# IN-17_tubes.net
KiCad netlist of a schematic drawn in EAGLE
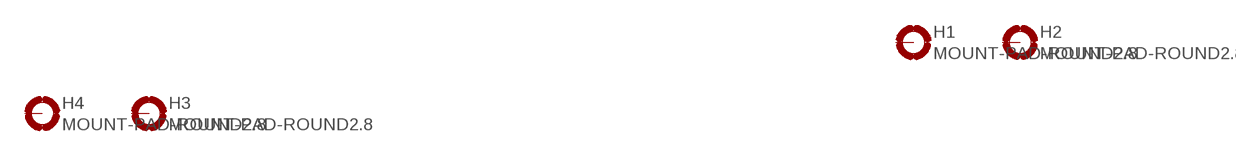
[diagram p0: schematic, sheet 1, part 1 of 2]
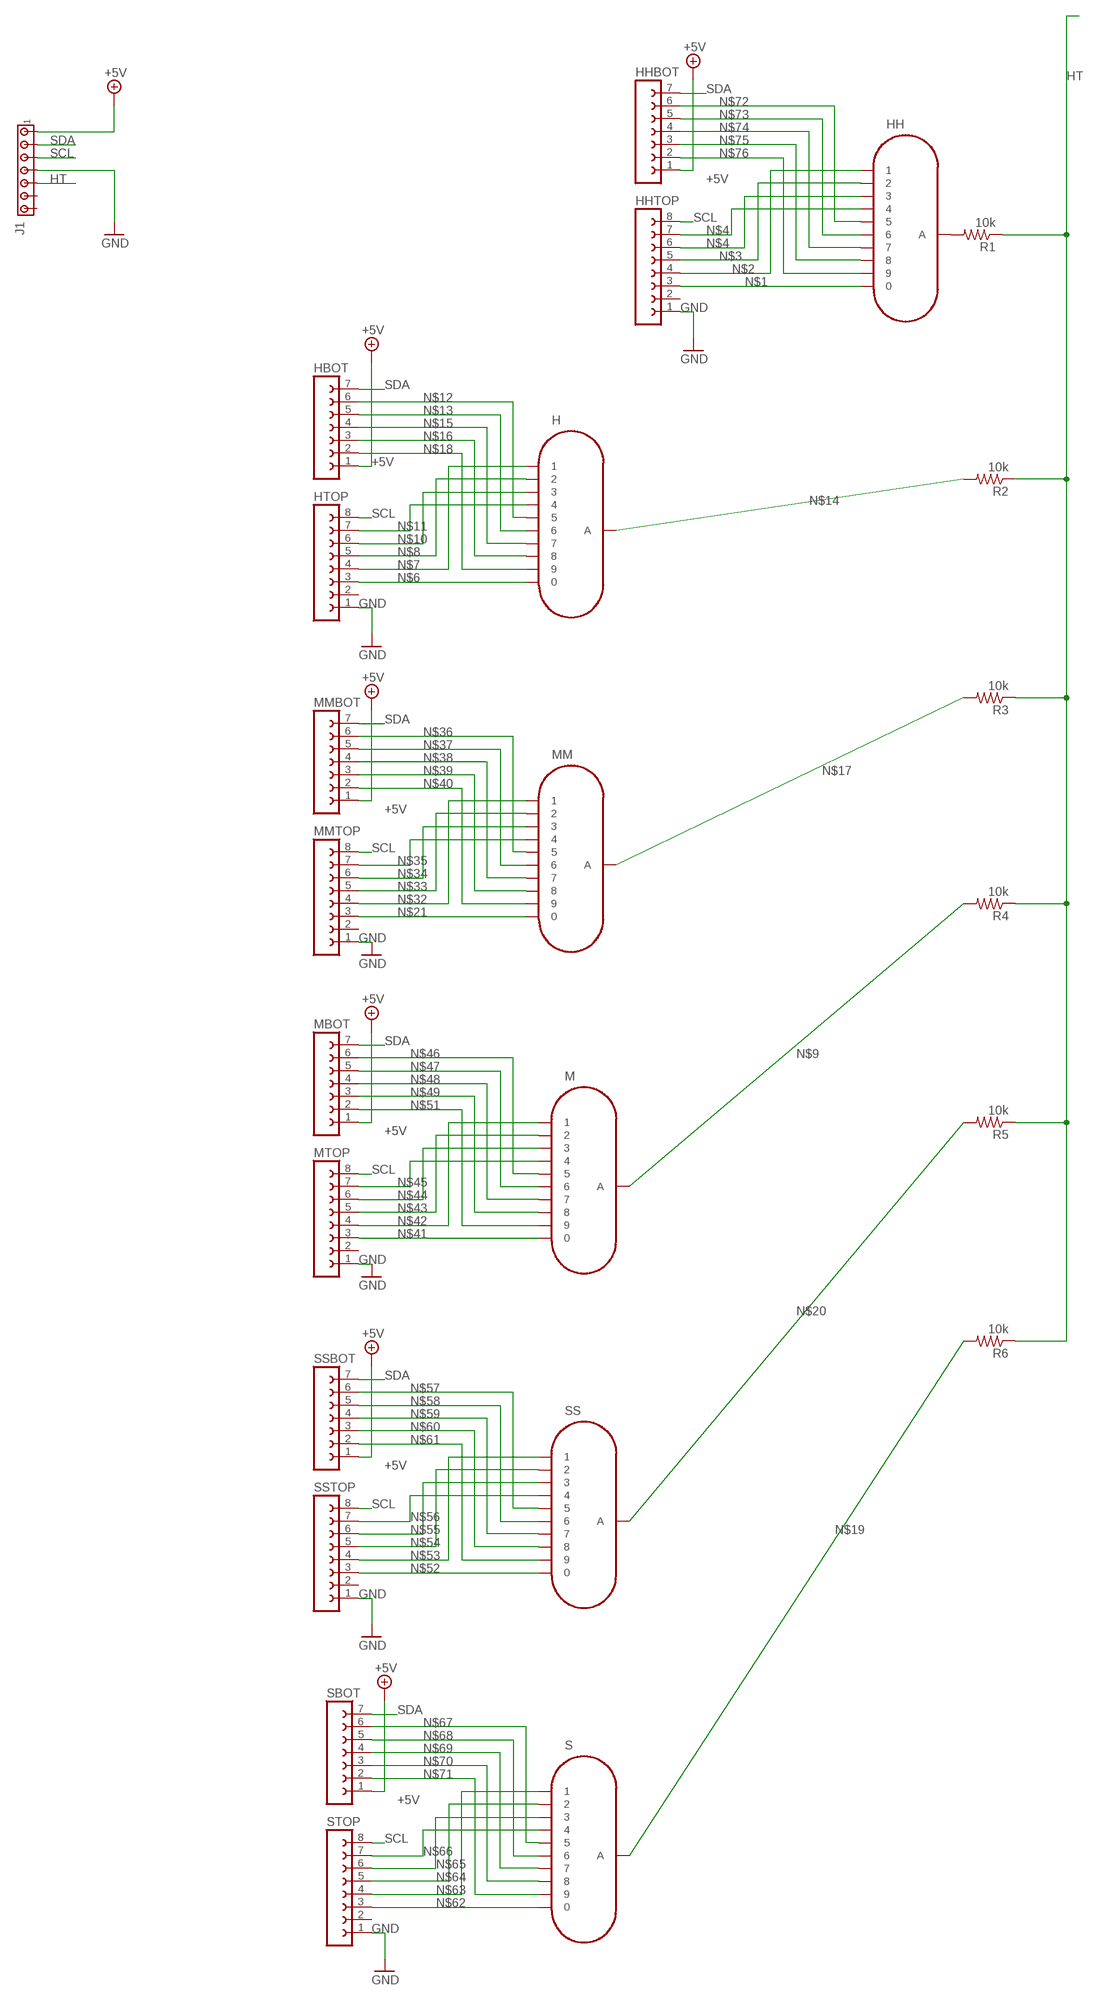
[diagram p1: schematic, sheet 1, part 2 of 2]

(export (version "E")
  (design (tool "Eeschema 10.0.6"))
  (components
    (comp (ref "H")
      (value "IN-17")
      (footprint "eagle-import:IN-17")
      (libsource (lib "eagle-import") (part "IN-17"))
    )
    (comp (ref "H1")
      (value "MOUNT-PAD-ROUND2.8")
      (footprint "eagle-import:2,8-PAD")
      (libsource (lib "eagle-import") (part "MOUNT-PAD-ROUND2.8"))
    )
    (comp (ref "H2")
      (value "MOUNT-PAD-ROUND2.8")
      (footprint "eagle-import:2,8-PAD")
      (libsource (lib "eagle-import") (part "MOUNT-PAD-ROUND2.8"))
    )
    (comp (ref "H3")
      (value "MOUNT-PAD-ROUND2.8")
      (footprint "eagle-import:2,8-PAD")
      (libsource (lib "eagle-import") (part "MOUNT-PAD-ROUND2.8"))
    )
    (comp (ref "H4")
      (value "MOUNT-PAD-ROUND2.8")
      (footprint "eagle-import:2,8-PAD")
      (libsource (lib "eagle-import") (part "MOUNT-PAD-ROUND2.8"))
    )
    (comp (ref "HBOT")
      (value "FE07-1")
      (footprint "eagle-import:FE07")
      (libsource (lib "eagle-import") (part "FE07-1"))
    )
    (comp (ref "HH")
      (value "IN-17")
      (footprint "eagle-import:IN-17")
      (libsource (lib "eagle-import") (part "IN-17"))
    )
    (comp (ref "HHBOT")
      (value "FE07-1")
      (footprint "eagle-import:FE07")
      (libsource (lib "eagle-import") (part "FE07-1"))
    )
    (comp (ref "HHTOP")
      (value "FE08-1")
      (footprint "eagle-import:FE08")
      (libsource (lib "eagle-import") (part "FE08-1"))
    )
    (comp (ref "HTOP")
      (value "FE08-1")
      (footprint "eagle-import:FE08")
      (libsource (lib "eagle-import") (part "FE08-1"))
    )
    (comp (ref "J1")
      (value "MTA07-100")
      (footprint "eagle-import:10X07MTA")
      (libsource (lib "eagle-import") (part "MTA07-100"))
    )
    (comp (ref "M")
      (value "IN-17")
      (footprint "eagle-import:IN-17")
      (libsource (lib "eagle-import") (part "IN-17"))
    )
    (comp (ref "MBOT")
      (value "FE07-1")
      (footprint "eagle-import:FE07")
      (libsource (lib "eagle-import") (part "FE07-1"))
    )
    (comp (ref "MM")
      (value "IN-17")
      (footprint "eagle-import:IN-17")
      (libsource (lib "eagle-import") (part "IN-17"))
    )
    (comp (ref "MMBOT")
      (value "FE07-1")
      (footprint "eagle-import:FE07")
      (libsource (lib "eagle-import") (part "FE07-1"))
    )
    (comp (ref "MMTOP")
      (value "FE08-1")
      (footprint "eagle-import:FE08")
      (libsource (lib "eagle-import") (part "FE08-1"))
    )
    (comp (ref "MTOP")
      (value "FE08-1")
      (footprint "eagle-import:FE08")
      (libsource (lib "eagle-import") (part "FE08-1"))
    )
    (comp (ref "R1")
      (value "10k")
      (footprint "eagle-import:M0805")
      (libsource (lib "eagle-import") (part "R-US_M0805"))
    )
    (comp (ref "R2")
      (value "10k")
      (footprint "eagle-import:M0805")
      (libsource (lib "eagle-import") (part "R-US_M0805"))
    )
    (comp (ref "R3")
      (value "10k")
      (footprint "eagle-import:M0805")
      (libsource (lib "eagle-import") (part "R-US_M0805"))
    )
    (comp (ref "R4")
      (value "10k")
      (footprint "eagle-import:M0805")
      (libsource (lib "eagle-import") (part "R-US_M0805"))
    )
    (comp (ref "R5")
      (value "10k")
      (footprint "eagle-import:M0805")
      (libsource (lib "eagle-import") (part "R-US_M0805"))
    )
    (comp (ref "R6")
      (value "10k")
      (footprint "eagle-import:M0805")
      (libsource (lib "eagle-import") (part "R-US_M0805"))
    )
    (comp (ref "S")
      (value "IN-17")
      (footprint "eagle-import:IN-17")
      (libsource (lib "eagle-import") (part "IN-17"))
    )
    (comp (ref "SBOT")
      (value "FE07-1")
      (footprint "eagle-import:FE07")
      (libsource (lib "eagle-import") (part "FE07-1"))
    )
    (comp (ref "SS")
      (value "IN-17")
      (footprint "eagle-import:IN-17")
      (libsource (lib "eagle-import") (part "IN-17"))
    )
    (comp (ref "SSBOT")
      (value "FE07-1")
      (footprint "eagle-import:FE07")
      (libsource (lib "eagle-import") (part "FE07-1"))
    )
    (comp (ref "SSTOP")
      (value "FE08-1")
      (footprint "eagle-import:FE08")
      (libsource (lib "eagle-import") (part "FE08-1"))
    )
    (comp (ref "STOP")
      (value "FE08-1")
      (footprint "eagle-import:FE08")
      (libsource (lib "eagle-import") (part "FE08-1"))
    )
  )
  (nets
    (net (code "1") (name "+5V") (class "Default")
      (node (ref "HBOT") (pin "1") (pinfunction "1_1") (pintype "passive"))
      (node (ref "HHBOT") (pin "1") (pinfunction "1_1") (pintype "passive"))
      (node (ref "J1") (pin "1") (pinfunction "1_1") (pintype "passive"))
      (node (ref "MBOT") (pin "1") (pinfunction "1_1") (pintype "passive"))
      (node (ref "MMBOT") (pin "1") (pinfunction "1_1") (pintype "passive"))
      (node (ref "SBOT") (pin "1") (pinfunction "1_1") (pintype "passive"))
      (node (ref "SSBOT") (pin "1") (pinfunction "1_1") (pintype "passive"))
    )
    (net (code "2") (name "/HT") (class "Default")
      (node (ref "J1") (pin "5") (pinfunction "5_5") (pintype "passive"))
      (node (ref "R1") (pin "1") (pinfunction "1_1") (pintype "passive"))
      (node (ref "R2") (pin "1") (pinfunction "1_1") (pintype "passive"))
      (node (ref "R3") (pin "1") (pinfunction "1_1") (pintype "passive"))
      (node (ref "R4") (pin "1") (pinfunction "1_1") (pintype "passive"))
      (node (ref "R5") (pin "1") (pinfunction "1_1") (pintype "passive"))
      (node (ref "R6") (pin "1") (pinfunction "1_1") (pintype "passive"))
    )
    (net (code "3") (name "/N$1") (class "Default")
      (node (ref "HH") (pin "0") (pinfunction "0_0") (pintype "bidirectional"))
      (node (ref "HHTOP") (pin "3") (pinfunction "3_3") (pintype "passive"))
    )
    (net (code "4") (name "/N$2") (class "Default")
      (node (ref "HH") (pin "1") (pinfunction "1_1") (pintype "bidirectional"))
      (node (ref "HHTOP") (pin "4") (pinfunction "4_4") (pintype "passive"))
    )
    (net (code "5") (name "/N$3") (class "Default")
      (node (ref "HH") (pin "2") (pinfunction "2_2") (pintype "bidirectional"))
      (node (ref "HHTOP") (pin "5") (pinfunction "5_5") (pintype "passive"))
    )
    (net (code "6") (name "/N$4") (class "Default")
      (node (ref "HH") (pin "3") (pinfunction "3_3") (pintype "bidirectional"))
      (node (ref "HHTOP") (pin "6") (pinfunction "6_6") (pintype "passive"))
    )
    (net (code "7") (name "/N$6") (class "Default")
      (node (ref "H") (pin "0") (pinfunction "0_0") (pintype "bidirectional"))
      (node (ref "HTOP") (pin "3") (pinfunction "3_3") (pintype "passive"))
    )
    (net (code "8") (name "/N$7") (class "Default")
      (node (ref "H") (pin "1") (pinfunction "1_1") (pintype "bidirectional"))
      (node (ref "HTOP") (pin "4") (pinfunction "4_4") (pintype "passive"))
    )
    (net (code "9") (name "/N$8") (class "Default")
      (node (ref "H") (pin "2") (pinfunction "2_2") (pintype "bidirectional"))
      (node (ref "HTOP") (pin "5") (pinfunction "5_5") (pintype "passive"))
    )
    (net (code "10") (name "/N$9") (class "Default")
      (node (ref "M") (pin "A") (pinfunction "A_A") (pintype "bidirectional"))
      (node (ref "R4") (pin "2") (pinfunction "2_2") (pintype "passive"))
    )
    (net (code "11") (name "/N$10") (class "Default")
      (node (ref "H") (pin "3") (pinfunction "3_3") (pintype "bidirectional"))
      (node (ref "HTOP") (pin "6") (pinfunction "6_6") (pintype "passive"))
    )
    (net (code "12") (name "/N$11") (class "Default")
      (node (ref "H") (pin "4") (pinfunction "4_4") (pintype "bidirectional"))
      (node (ref "HTOP") (pin "7") (pinfunction "7_7") (pintype "passive"))
    )
    (net (code "13") (name "/N$12") (class "Default")
      (node (ref "H") (pin "5") (pinfunction "5_5") (pintype "bidirectional"))
      (node (ref "HBOT") (pin "6") (pinfunction "6_6") (pintype "passive"))
    )
    (net (code "14") (name "/N$13") (class "Default")
      (node (ref "H") (pin "6") (pinfunction "6_6") (pintype "bidirectional"))
      (node (ref "HBOT") (pin "5") (pinfunction "5_5") (pintype "passive"))
    )
    (net (code "15") (name "/N$14") (class "Default")
      (node (ref "H") (pin "A") (pinfunction "A_A") (pintype "bidirectional"))
      (node (ref "R2") (pin "2") (pinfunction "2_2") (pintype "passive"))
    )
    (net (code "16") (name "/N$15") (class "Default")
      (node (ref "H") (pin "7") (pinfunction "7_7") (pintype "bidirectional"))
      (node (ref "HBOT") (pin "4") (pinfunction "4_4") (pintype "passive"))
    )
    (net (code "17") (name "/N$16") (class "Default")
      (node (ref "H") (pin "8") (pinfunction "8_8") (pintype "bidirectional"))
      (node (ref "HBOT") (pin "3") (pinfunction "3_3") (pintype "passive"))
    )
    (net (code "18") (name "/N$17") (class "Default")
      (node (ref "MM") (pin "A") (pinfunction "A_A") (pintype "bidirectional"))
      (node (ref "R3") (pin "2") (pinfunction "2_2") (pintype "passive"))
    )
    (net (code "19") (name "/N$18") (class "Default")
      (node (ref "H") (pin "9") (pinfunction "9_9") (pintype "bidirectional"))
      (node (ref "HBOT") (pin "2") (pinfunction "2_2") (pintype "passive"))
    )
    (net (code "20") (name "/N$19") (class "Default")
      (node (ref "R6") (pin "2") (pinfunction "2_2") (pintype "passive"))
      (node (ref "S") (pin "A") (pinfunction "A_A") (pintype "bidirectional"))
    )
    (net (code "21") (name "/N$20") (class "Default")
      (node (ref "R5") (pin "2") (pinfunction "2_2") (pintype "passive"))
      (node (ref "SS") (pin "A") (pinfunction "A_A") (pintype "bidirectional"))
    )
    (net (code "22") (name "/N$21") (class "Default")
      (node (ref "MM") (pin "0") (pinfunction "0_0") (pintype "bidirectional"))
      (node (ref "MMTOP") (pin "3") (pinfunction "3_3") (pintype "passive"))
    )
    (net (code "23") (name "/N$32") (class "Default")
      (node (ref "MM") (pin "1") (pinfunction "1_1") (pintype "bidirectional"))
      (node (ref "MMTOP") (pin "4") (pinfunction "4_4") (pintype "passive"))
    )
    (net (code "24") (name "/N$33") (class "Default")
      (node (ref "MM") (pin "2") (pinfunction "2_2") (pintype "bidirectional"))
      (node (ref "MMTOP") (pin "5") (pinfunction "5_5") (pintype "passive"))
    )
    (net (code "25") (name "/N$34") (class "Default")
      (node (ref "MM") (pin "3") (pinfunction "3_3") (pintype "bidirectional"))
      (node (ref "MMTOP") (pin "6") (pinfunction "6_6") (pintype "passive"))
    )
    (net (code "26") (name "/N$35") (class "Default")
      (node (ref "MM") (pin "4") (pinfunction "4_4") (pintype "bidirectional"))
      (node (ref "MMTOP") (pin "7") (pinfunction "7_7") (pintype "passive"))
    )
    (net (code "27") (name "/N$36") (class "Default")
      (node (ref "MM") (pin "5") (pinfunction "5_5") (pintype "bidirectional"))
      (node (ref "MMBOT") (pin "6") (pinfunction "6_6") (pintype "passive"))
    )
    (net (code "28") (name "/N$37") (class "Default")
      (node (ref "MM") (pin "6") (pinfunction "6_6") (pintype "bidirectional"))
      (node (ref "MMBOT") (pin "5") (pinfunction "5_5") (pintype "passive"))
    )
    (net (code "29") (name "/N$38") (class "Default")
      (node (ref "MM") (pin "7") (pinfunction "7_7") (pintype "bidirectional"))
      (node (ref "MMBOT") (pin "4") (pinfunction "4_4") (pintype "passive"))
    )
    (net (code "30") (name "/N$39") (class "Default")
      (node (ref "MM") (pin "8") (pinfunction "8_8") (pintype "bidirectional"))
      (node (ref "MMBOT") (pin "3") (pinfunction "3_3") (pintype "passive"))
    )
    (net (code "31") (name "/N$40") (class "Default")
      (node (ref "MM") (pin "9") (pinfunction "9_9") (pintype "bidirectional"))
      (node (ref "MMBOT") (pin "2") (pinfunction "2_2") (pintype "passive"))
    )
    (net (code "32") (name "/N$41") (class "Default")
      (node (ref "M") (pin "0") (pinfunction "0_0") (pintype "bidirectional"))
      (node (ref "MTOP") (pin "3") (pinfunction "3_3") (pintype "passive"))
    )
    (net (code "33") (name "/N$42") (class "Default")
      (node (ref "M") (pin "1") (pinfunction "1_1") (pintype "bidirectional"))
      (node (ref "MTOP") (pin "4") (pinfunction "4_4") (pintype "passive"))
    )
    (net (code "34") (name "/N$43") (class "Default")
      (node (ref "M") (pin "2") (pinfunction "2_2") (pintype "bidirectional"))
      (node (ref "MTOP") (pin "5") (pinfunction "5_5") (pintype "passive"))
    )
    (net (code "35") (name "/N$44") (class "Default")
      (node (ref "M") (pin "3") (pinfunction "3_3") (pintype "bidirectional"))
      (node (ref "MTOP") (pin "6") (pinfunction "6_6") (pintype "passive"))
    )
    (net (code "36") (name "/N$45") (class "Default")
      (node (ref "M") (pin "4") (pinfunction "4_4") (pintype "bidirectional"))
      (node (ref "MTOP") (pin "7") (pinfunction "7_7") (pintype "passive"))
    )
    (net (code "37") (name "/N$46") (class "Default")
      (node (ref "M") (pin "5") (pinfunction "5_5") (pintype "bidirectional"))
      (node (ref "MBOT") (pin "6") (pinfunction "6_6") (pintype "passive"))
    )
    (net (code "38") (name "/N$47") (class "Default")
      (node (ref "M") (pin "6") (pinfunction "6_6") (pintype "bidirectional"))
      (node (ref "MBOT") (pin "5") (pinfunction "5_5") (pintype "passive"))
    )
    (net (code "39") (name "/N$48") (class "Default")
      (node (ref "M") (pin "7") (pinfunction "7_7") (pintype "bidirectional"))
      (node (ref "MBOT") (pin "4") (pinfunction "4_4") (pintype "passive"))
    )
    (net (code "40") (name "/N$49") (class "Default")
      (node (ref "M") (pin "8") (pinfunction "8_8") (pintype "bidirectional"))
      (node (ref "MBOT") (pin "3") (pinfunction "3_3") (pintype "passive"))
    )
    (net (code "41") (name "/N$51") (class "Default")
      (node (ref "M") (pin "9") (pinfunction "9_9") (pintype "bidirectional"))
      (node (ref "MBOT") (pin "2") (pinfunction "2_2") (pintype "passive"))
    )
    (net (code "42") (name "/N$52") (class "Default")
      (node (ref "SS") (pin "0") (pinfunction "0_0") (pintype "bidirectional"))
      (node (ref "SSTOP") (pin "3") (pinfunction "3_3") (pintype "passive"))
    )
    (net (code "43") (name "/N$53") (class "Default")
      (node (ref "SS") (pin "1") (pinfunction "1_1") (pintype "bidirectional"))
      (node (ref "SSTOP") (pin "4") (pinfunction "4_4") (pintype "passive"))
    )
    (net (code "44") (name "/N$54") (class "Default")
      (node (ref "SS") (pin "2") (pinfunction "2_2") (pintype "bidirectional"))
      (node (ref "SSTOP") (pin "5") (pinfunction "5_5") (pintype "passive"))
    )
    (net (code "45") (name "/N$55") (class "Default")
      (node (ref "SS") (pin "3") (pinfunction "3_3") (pintype "bidirectional"))
      (node (ref "SSTOP") (pin "6") (pinfunction "6_6") (pintype "passive"))
    )
    (net (code "46") (name "/N$56") (class "Default")
      (node (ref "SS") (pin "4") (pinfunction "4_4") (pintype "bidirectional"))
      (node (ref "SSTOP") (pin "7") (pinfunction "7_7") (pintype "passive"))
    )
    (net (code "47") (name "/N$57") (class "Default")
      (node (ref "SS") (pin "5") (pinfunction "5_5") (pintype "bidirectional"))
      (node (ref "SSBOT") (pin "6") (pinfunction "6_6") (pintype "passive"))
    )
    (net (code "48") (name "/N$58") (class "Default")
      (node (ref "SS") (pin "6") (pinfunction "6_6") (pintype "bidirectional"))
      (node (ref "SSBOT") (pin "5") (pinfunction "5_5") (pintype "passive"))
    )
    (net (code "49") (name "/N$59") (class "Default")
      (node (ref "SS") (pin "7") (pinfunction "7_7") (pintype "bidirectional"))
      (node (ref "SSBOT") (pin "4") (pinfunction "4_4") (pintype "passive"))
    )
    (net (code "50") (name "/N$60") (class "Default")
      (node (ref "SS") (pin "8") (pinfunction "8_8") (pintype "bidirectional"))
      (node (ref "SSBOT") (pin "3") (pinfunction "3_3") (pintype "passive"))
    )
    (net (code "51") (name "/N$61") (class "Default")
      (node (ref "SS") (pin "9") (pinfunction "9_9") (pintype "bidirectional"))
      (node (ref "SSBOT") (pin "2") (pinfunction "2_2") (pintype "passive"))
    )
    (net (code "52") (name "/N$62") (class "Default")
      (node (ref "S") (pin "0") (pinfunction "0_0") (pintype "bidirectional"))
      (node (ref "STOP") (pin "3") (pinfunction "3_3") (pintype "passive"))
    )
    (net (code "53") (name "/N$63") (class "Default")
      (node (ref "S") (pin "1") (pinfunction "1_1") (pintype "bidirectional"))
      (node (ref "STOP") (pin "4") (pinfunction "4_4") (pintype "passive"))
    )
    (net (code "54") (name "/N$64") (class "Default")
      (node (ref "S") (pin "2") (pinfunction "2_2") (pintype "bidirectional"))
      (node (ref "STOP") (pin "5") (pinfunction "5_5") (pintype "passive"))
    )
    (net (code "55") (name "/N$65") (class "Default")
      (node (ref "S") (pin "3") (pinfunction "3_3") (pintype "bidirectional"))
      (node (ref "STOP") (pin "6") (pinfunction "6_6") (pintype "passive"))
    )
    (net (code "56") (name "/N$66") (class "Default")
      (node (ref "S") (pin "4") (pinfunction "4_4") (pintype "bidirectional"))
      (node (ref "STOP") (pin "7") (pinfunction "7_7") (pintype "passive"))
    )
    (net (code "57") (name "/N$67") (class "Default")
      (node (ref "S") (pin "5") (pinfunction "5_5") (pintype "bidirectional"))
      (node (ref "SBOT") (pin "6") (pinfunction "6_6") (pintype "passive"))
    )
    (net (code "58") (name "/N$68") (class "Default")
      (node (ref "S") (pin "6") (pinfunction "6_6") (pintype "bidirectional"))
      (node (ref "SBOT") (pin "5") (pinfunction "5_5") (pintype "passive"))
    )
    (net (code "59") (name "/N$69") (class "Default")
      (node (ref "S") (pin "7") (pinfunction "7_7") (pintype "bidirectional"))
      (node (ref "SBOT") (pin "4") (pinfunction "4_4") (pintype "passive"))
    )
    (net (code "60") (name "/N$70") (class "Default")
      (node (ref "S") (pin "8") (pinfunction "8_8") (pintype "bidirectional"))
      (node (ref "SBOT") (pin "3") (pinfunction "3_3") (pintype "passive"))
    )
    (net (code "61") (name "/N$71") (class "Default")
      (node (ref "S") (pin "9") (pinfunction "9_9") (pintype "bidirectional"))
      (node (ref "SBOT") (pin "2") (pinfunction "2_2") (pintype "passive"))
    )
    (net (code "62") (name "/N$72") (class "Default")
      (node (ref "HH") (pin "5") (pinfunction "5_5") (pintype "bidirectional"))
      (node (ref "HHBOT") (pin "6") (pinfunction "6_6") (pintype "passive"))
    )
    (net (code "63") (name "/N$73") (class "Default")
      (node (ref "HH") (pin "6") (pinfunction "6_6") (pintype "bidirectional"))
      (node (ref "HHBOT") (pin "5") (pinfunction "5_5") (pintype "passive"))
    )
    (net (code "64") (name "/N$74") (class "Default")
      (node (ref "HH") (pin "7") (pinfunction "7_7") (pintype "bidirectional"))
      (node (ref "HHBOT") (pin "4") (pinfunction "4_4") (pintype "passive"))
    )
    (net (code "65") (name "/N$75") (class "Default")
      (node (ref "HH") (pin "8") (pinfunction "8_8") (pintype "bidirectional"))
      (node (ref "HHBOT") (pin "3") (pinfunction "3_3") (pintype "passive"))
    )
    (net (code "66") (name "/N$76") (class "Default")
      (node (ref "HH") (pin "9") (pinfunction "9_9") (pintype "bidirectional"))
      (node (ref "HHBOT") (pin "2") (pinfunction "2_2") (pintype "passive"))
    )
    (net (code "67") (name "/SCL") (class "Default")
      (node (ref "HHTOP") (pin "8") (pinfunction "8_8") (pintype "passive"))
      (node (ref "HTOP") (pin "8") (pinfunction "8_8") (pintype "passive"))
      (node (ref "J1") (pin "3") (pinfunction "3_3") (pintype "passive"))
      (node (ref "MMTOP") (pin "8") (pinfunction "8_8") (pintype "passive"))
      (node (ref "MTOP") (pin "8") (pinfunction "8_8") (pintype "passive"))
      (node (ref "SSTOP") (pin "8") (pinfunction "8_8") (pintype "passive"))
      (node (ref "STOP") (pin "8") (pinfunction "8_8") (pintype "passive"))
    )
    (net (code "68") (name "/SDA") (class "Default")
      (node (ref "HBOT") (pin "7") (pinfunction "7_7") (pintype "passive"))
      (node (ref "HHBOT") (pin "7") (pinfunction "7_7") (pintype "passive"))
      (node (ref "J1") (pin "2") (pinfunction "2_2") (pintype "passive"))
      (node (ref "MBOT") (pin "7") (pinfunction "7_7") (pintype "passive"))
      (node (ref "MMBOT") (pin "7") (pinfunction "7_7") (pintype "passive"))
      (node (ref "SBOT") (pin "7") (pinfunction "7_7") (pintype "passive"))
      (node (ref "SSBOT") (pin "7") (pinfunction "7_7") (pintype "passive"))
    )
    (net (code "69") (name "GND") (class "Default")
      (node (ref "HHTOP") (pin "1") (pinfunction "1_1") (pintype "passive"))
      (node (ref "HTOP") (pin "1") (pinfunction "1_1") (pintype "passive"))
      (node (ref "J1") (pin "4") (pinfunction "4_4") (pintype "passive"))
      (node (ref "MMTOP") (pin "1") (pinfunction "1_1") (pintype "passive"))
      (node (ref "MTOP") (pin "1") (pinfunction "1_1") (pintype "passive"))
      (node (ref "SSTOP") (pin "1") (pinfunction "1_1") (pintype "passive"))
      (node (ref "STOP") (pin "1") (pinfunction "1_1") (pintype "passive"))
    )
    (net (code "70") (name "Net-(HH-Pad4)") (class "Default")
      (node (ref "HH") (pin "4") (pinfunction "4_4") (pintype "bidirectional"))
      (node (ref "HHTOP") (pin "7") (pinfunction "7_7") (pintype "passive"))
    )
    (net (code "71") (name "Net-(HH-PadA)") (class "Default")
      (node (ref "HH") (pin "A") (pinfunction "A_A") (pintype "bidirectional"))
      (node (ref "R1") (pin "2") (pinfunction "2_2") (pintype "passive"))
    )
    (net (code "72") (name "unconnected-(H1-MOUNT-PadB2,8)") (class "Default")
      (node (ref "H1") (pin "B2,8") (pinfunction "MOUNT_B2,8") (pintype "passive"))
    )
    (net (code "73") (name "unconnected-(H2-MOUNT-PadB2,8)") (class "Default")
      (node (ref "H2") (pin "B2,8") (pinfunction "MOUNT_B2,8") (pintype "passive"))
    )
    (net (code "74") (name "unconnected-(H3-MOUNT-PadB2,8)") (class "Default")
      (node (ref "H3") (pin "B2,8") (pinfunction "MOUNT_B2,8") (pintype "passive"))
    )
    (net (code "75") (name "unconnected-(H4-MOUNT-PadB2,8)") (class "Default")
      (node (ref "H4") (pin "B2,8") (pinfunction "MOUNT_B2,8") (pintype "passive"))
    )
    (net (code "76") (name "unconnected-(HHTOP-Pad2)") (class "Default")
      (node (ref "HHTOP") (pin "2") (pinfunction "2_2") (pintype "passive"))
    )
    (net (code "77") (name "unconnected-(HTOP-Pad2)") (class "Default")
      (node (ref "HTOP") (pin "2") (pinfunction "2_2") (pintype "passive"))
    )
    (net (code "78") (name "unconnected-(J1-Pad6)") (class "Default")
      (node (ref "J1") (pin "6") (pinfunction "6_6") (pintype "passive"))
    )
    (net (code "79") (name "unconnected-(J1-Pad7)") (class "Default")
      (node (ref "J1") (pin "7") (pinfunction "7_7") (pintype "passive"))
    )
    (net (code "80") (name "unconnected-(MMTOP-Pad2)") (class "Default")
      (node (ref "MMTOP") (pin "2") (pinfunction "2_2") (pintype "passive"))
    )
    (net (code "81") (name "unconnected-(MTOP-Pad2)") (class "Default")
      (node (ref "MTOP") (pin "2") (pinfunction "2_2") (pintype "passive"))
    )
    (net (code "82") (name "unconnected-(SSTOP-Pad2)") (class "Default")
      (node (ref "SSTOP") (pin "2") (pinfunction "2_2") (pintype "passive"))
    )
    (net (code "83") (name "unconnected-(STOP-Pad2)") (class "Default")
      (node (ref "STOP") (pin "2") (pinfunction "2_2") (pintype "passive"))
    )
  )
)
